# CPU.net
KiCad netlist of a schematic drawn in Altium Designer
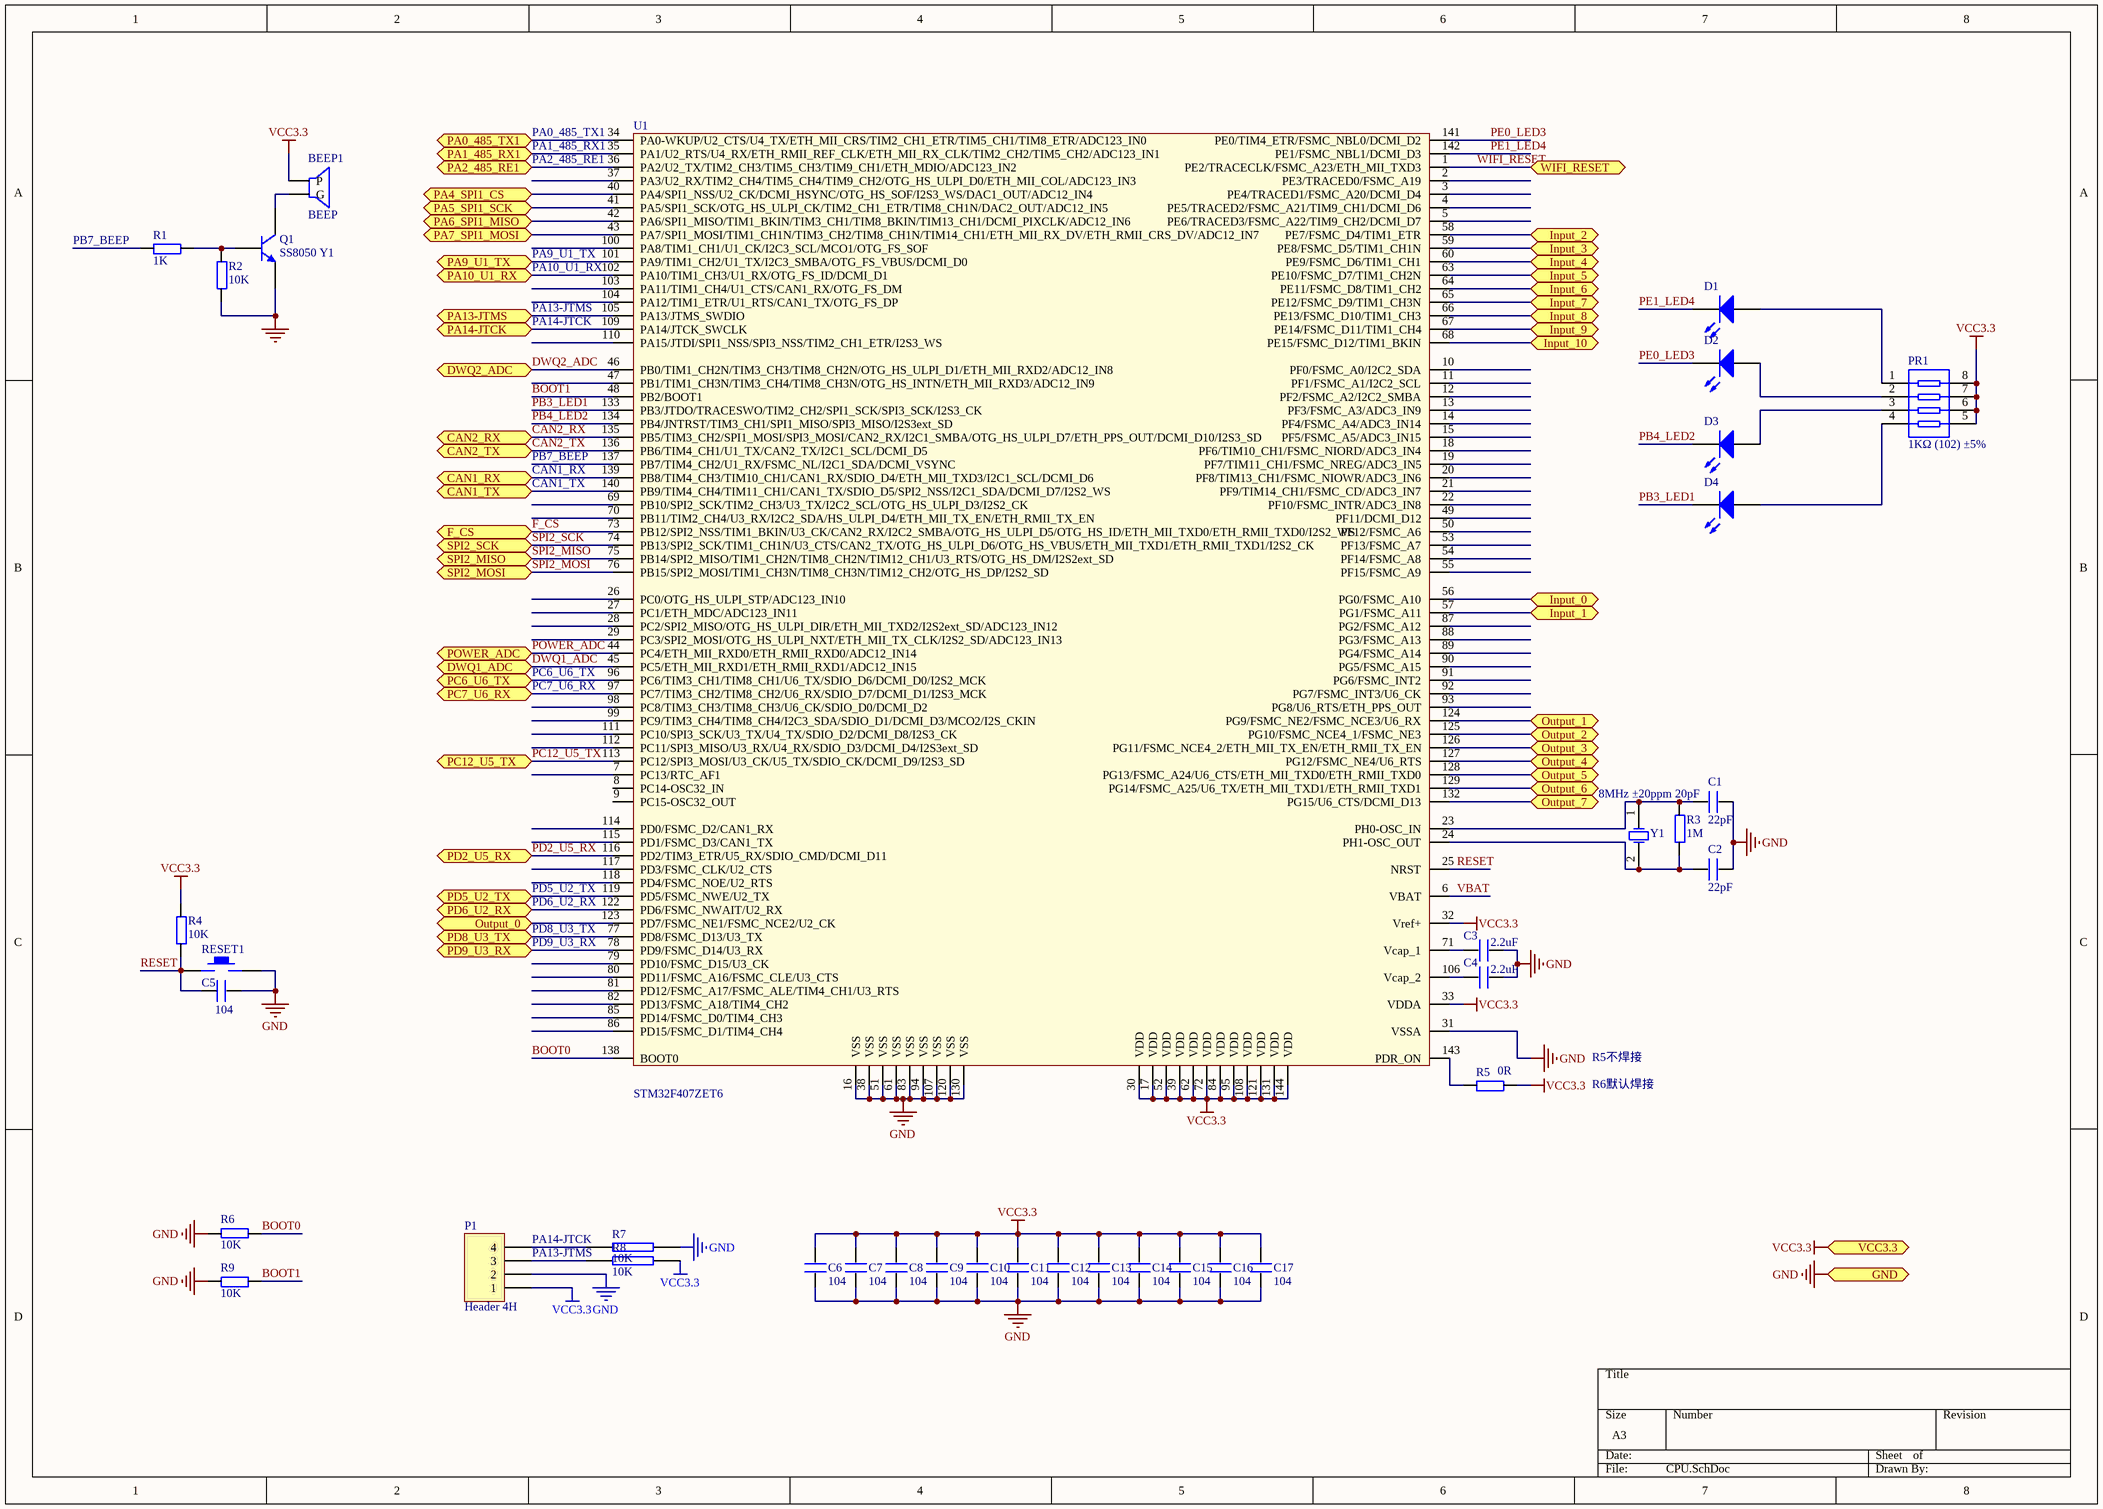
[diagram p0: CPU.SchDoc]

(export (version "E")
  (design (tool "Eeschema 10.0.6"))
  (components
    (comp (ref "BEEP1") (value "BEEP") (footprint "BELL-5") (libsource (lib "WarShip V3_SCH") (part "BEEP")))
    (comp (ref "C1")
      (value "22pF")
      (footprint "0603_C")
      (libsource (lib "Explorer STM32F407封装库") (part "C_3"))
    )
    (comp (ref "C2")
      (value "22pF")
      (footprint "0603_C")
      (libsource (lib "Explorer STM32F407封装库") (part "C_3"))
    )
    (comp (ref "C3")
      (value "2.2uF")
      (footprint "0603_C")
      (libsource (lib "Explorer STM32F407封装库") (part "C"))
    )
    (comp (ref "C4")
      (value "2.2uF")
      (footprint "0603_C")
      (libsource (lib "Explorer STM32F407封装库") (part "C"))
    )
    (comp (ref "C5") (value "104") (footprint "0603_C") (libsource (lib "Explorer STM32F407封装库") (part "C")))
    (comp (ref "C6") (value "104") (footprint "0603_C") (libsource (lib "WarShip V3_SCH") (part "C")))
    (comp (ref "C7") (value "104") (footprint "0603_C") (libsource (lib "WarShip V3_SCH") (part "C")))
    (comp (ref "C8") (value "104") (footprint "0603_C") (libsource (lib "WarShip V3_SCH") (part "C")))
    (comp (ref "C9") (value "104") (footprint "0603_C") (libsource (lib "WarShip V3_SCH") (part "C")))
    (comp (ref "C10") (value "104") (footprint "0603_C") (libsource (lib "WarShip V3_SCH") (part "C")))
    (comp (ref "C11") (value "104") (footprint "0603_C") (libsource (lib "WarShip V3_SCH") (part "C")))
    (comp (ref "C12") (value "104") (footprint "0603_C") (libsource (lib "WarShip V3_SCH") (part "C")))
    (comp (ref "C13") (value "104") (footprint "0603_C") (libsource (lib "WarShip V3_SCH") (part "C")))
    (comp (ref "C14") (value "104") (footprint "0603_C") (libsource (lib "WarShip V3_SCH") (part "C")))
    (comp (ref "C15") (value "104") (footprint "0603_C") (libsource (lib "WarShip V3_SCH") (part "C")))
    (comp (ref "C16") (value "104") (footprint "0603_C") (libsource (lib "WarShip V3_SCH") (part "C")))
    (comp (ref "C17") (value "104") (footprint "0603_C") (libsource (lib "WarShip V3_SCH") (part "C")))
    (comp (ref "D1")
      (value "红灯 0805")
      (footprint "LC-0805_LED_S1")
      (description "Typical INFRARED GaAs LED")
      (fields (field (name "PUBLISHER") "Altium Limited"))
      (libsource (lib "继电器板_1") (part "LED0"))
    )
    (comp (ref "D2")
      (value "红灯 0805")
      (footprint "LC-0805_LED_S1")
      (description "Typical INFRARED GaAs LED")
      (fields (field (name "PUBLISHER") "Altium Limited"))
      (libsource (lib "继电器板_1") (part "LED0"))
    )
    (comp (ref "D3")
      (value "红灯 0805")
      (footprint "LC-0805_LED_S1")
      (description "Typical INFRARED GaAs LED")
      (fields (field (name "PUBLISHER") "Altium Limited"))
      (libsource (lib "继电器板_1") (part "LED0"))
    )
    (comp (ref "D4")
      (value "红灯 0805")
      (footprint "LC-0805_LED_S1")
      (description "Typical INFRARED GaAs LED")
      (fields (field (name "PUBLISHER") "Altium Limited"))
      (libsource (lib "继电器板_1") (part "LED0"))
    )
    (comp (ref "P1")
      (value "Header 4H")
      (footprint "IDE4")
      (description "Header, 4-Pin, Right Angle")
      (fields (field (name "PUBLISHER") "Altium Limited"))
      (libsource (lib "Miscellaneous Connectors") (part "Header 4H"))
    )
    (comp (ref "PR1")
      (value "1KΩ (102) ±5%")
      (footprint "0603_Rx4")
      (description "贴片排阻")
      (libsource (lib "Miscellaneous Devices LC") (part "0603*4  1KΩ (102) 5%"))
    )
    (comp (ref "Q1")
      (value "SS8050 Y1")
      (footprint "SOT-23(SOT-23-3)")
      (description "三极管")
      (libsource (lib "Miscellaneous Devices LC") (part "SOT-23 SS8050 Y1"))
    )
    (comp (ref "R1") (value "1K") (footprint "0603_R") (libsource (lib "WarShip V3_SCH") (part "R")))
    (comp (ref "R2") (value "10K") (footprint "0603_R") (libsource (lib "WarShip V3_SCH") (part "R")))
    (comp (ref "R3") (value "1M") (footprint "0603_R") (libsource (lib "Explorer STM32F407封装库") (part "R")))
    (comp (ref "R4")
      (value "10K")
      (footprint "0603_R")
      (libsource (lib "Explorer STM32F407封装库") (part "R_2"))
    )
    (comp (ref "R5") (value "0R") (footprint "0603_R") (libsource (lib "Explorer STM32F407封装库") (part "R_2")))
    (comp (ref "R6")
      (value "10K")
      (footprint "0603_R")
      (libsource (lib "Explorer STM32F407封装库") (part "R_1"))
    )
    (comp (ref "R7") (value "10K") (footprint "0603_R") (libsource (lib "*") (part "RES2")))
    (comp (ref "R8") (value "10K") (footprint "0603_R") (libsource (lib "*") (part "RES2")))
    (comp (ref "R9")
      (value "10K")
      (footprint "0603_R")
      (libsource (lib "Explorer STM32F407封装库") (part "R_1"))
    )
    (comp (ref "RESET1")
      (value "KEY_M")
      (footprint "SW_PB2_A1")
      (libsource (lib "Explorer STM32F407封装库") (part "KEY_M"))
    )
    (comp (ref "U1")
      (value "STM32F407ZET6")
      (footprint "LQFP-144_20x20x05P")
      (libsource (lib "Explorer STM32F407封装库") (part "STM32F407ZET6"))
    )
    (comp (ref "Y1")
      (value "8MHz ±20ppm 20pF")
      (footprint "SMD-5032_2P")
      (description "贴片晶振")
      (libsource (lib "Miscellaneous Devices LC") (part "SMD-5032_2P 8MHz 20ppm 20pF"))
    )
  )
  (nets
    (net (code "1") (name "/BOOT0") (class "Default")
      (node (ref "R6") (pin "1") (pintype "passive"))
      (node (ref "U1") (pin "138") (pinfunction "BOOT0_138") (pintype "passive"))
    )
    (net (code "2") (name "/BOOT1") (class "Default")
      (node (ref "R9") (pin "2") (pintype "passive"))
      (node (ref "U1") (pin "48") (pinfunction "PB2/BOOT1_48") (pintype "passive"))
    )
    (net (code "3") (name "/CAN1_RX") (class "Default")
      (node (ref "U1") (pin "139") (pinfunction "PB8/TIM4_CH3/TIM10_CH1/CAN1_RX/SDIO_D4/ETH_MII_TXD3/I2C1_SCL/DCMI_D6_139") (pintype "passive"))
    )
    (net (code "4") (name "/CAN1_TX") (class "Default")
      (node (ref "U1") (pin "140") (pinfunction "PB9/TIM4_CH4/TIM11_CH1/CAN1_TX/SDIO_D5/SPI2_NSS/I2C1_SDA/DCMI_D7/I2S2_WS_140") (pintype "passive"))
    )
    (net (code "5") (name "/CAN2_RX") (class "Default")
      (node (ref "U1") (pin "135") (pinfunction "PB5/TIM3_CH2/SPI1_MOSI/SPI3_MOSI/CAN2_RX/I2C1_SMBA/OTG_HS_ULPI_D7/ETH_PPS_OUT/DCMI_D10/I2S3_SD_135") (pintype "passive"))
    )
    (net (code "6") (name "/CAN2_TX") (class "Default")
      (node (ref "U1") (pin "136") (pinfunction "PB6/TIM4_CH1/U1_TX/CAN2_TX/I2C1_SCL/DCMI_D5_136") (pintype "passive"))
    )
    (net (code "7") (name "/DWQ1_ADC") (class "Default")
      (node (ref "U1") (pin "45") (pinfunction "PC5/ETH_MII_RXD1/ETH_RMII_RXD1/ADC12_IN15_45") (pintype "passive"))
    )
    (net (code "8") (name "/DWQ2_ADC") (class "Default")
      (node (ref "U1") (pin "46") (pinfunction "PB0/TIM1_CH2N/TIM3_CH3/TIM8_CH2N/OTG_HS_ULPI_D1/ETH_MII_RXD2/ADC12_IN8_46") (pintype "passive"))
    )
    (net (code "9") (name "/F_CS") (class "Default")
      (node (ref "U1") (pin "73") (pinfunction "PB12/SPI2_NSS/TIM1_BKIN/U3_CK/CAN2_RX/I2C2_SMBA/OTG_HS_ULPI_D5/OTG_HS_ID/ETH_MII_TXD0/ETH_RMII_TXD0/I2S2_WS_73") (pintype "passive"))
    )
    (net (code "10") (name "/Input_0") (class "Default")
      (node (ref "U1") (pin "56") (pinfunction "PG0/FSMC_A10_56") (pintype "passive"))
    )
    (net (code "11") (name "/Input_1") (class "Default")
      (node (ref "U1") (pin "57") (pinfunction "PG1/FSMC_A11_57") (pintype "passive"))
    )
    (net (code "12") (name "/Input_2") (class "Default")
      (node (ref "U1") (pin "58") (pinfunction "PE7/FSMC_D4/TIM1_ETR_58") (pintype "passive"))
    )
    (net (code "13") (name "/Input_3") (class "Default")
      (node (ref "U1") (pin "59") (pinfunction "PE8/FSMC_D5/TIM1_CH1N_59") (pintype "passive"))
    )
    (net (code "14") (name "/Input_4") (class "Default")
      (node (ref "U1") (pin "60") (pinfunction "PE9/FSMC_D6/TIM1_CH1_60") (pintype "passive"))
    )
    (net (code "15") (name "/Input_5") (class "Default")
      (node (ref "U1") (pin "63") (pinfunction "PE10/FSMC_D7/TIM1_CH2N_63") (pintype "passive"))
    )
    (net (code "16") (name "/Input_6") (class "Default")
      (node (ref "U1") (pin "64") (pinfunction "PE11/FSMC_D8/TIM1_CH2_64") (pintype "passive"))
    )
    (net (code "17") (name "/Input_7") (class "Default")
      (node (ref "U1") (pin "65") (pinfunction "PE12/FSMC_D9/TIM1_CH3N_65") (pintype "passive"))
    )
    (net (code "18") (name "/Input_8") (class "Default")
      (node (ref "U1") (pin "66") (pinfunction "PE13/FSMC_D10/TIM1_CH3_66") (pintype "passive"))
    )
    (net (code "19") (name "/Input_9") (class "Default")
      (node (ref "U1") (pin "67") (pinfunction "PE14/FSMC_D11/TIM1_CH4_67") (pintype "passive"))
    )
    (net (code "20") (name "/Input_10") (class "Default")
      (node (ref "U1") (pin "68") (pinfunction "PE15/FSMC_D12/TIM1_BKIN_68") (pintype "passive"))
    )
    (net (code "21") (name "/Output_0") (class "Default")
      (node (ref "U1") (pin "123") (pinfunction "PD7/FSMC_NE1/FSMC_NCE2/U2_CK_123") (pintype "passive"))
    )
    (net (code "22") (name "/Output_1") (class "Default")
      (node (ref "U1") (pin "124") (pinfunction "PG9/FSMC_NE2/FSMC_NCE3/U6_RX_124") (pintype "passive"))
    )
    (net (code "23") (name "/Output_2") (class "Default")
      (node (ref "U1") (pin "125") (pinfunction "PG10/FSMC_NCE4_1/FSMC_NE3_125") (pintype "passive"))
    )
    (net (code "24") (name "/Output_3") (class "Default")
      (node (ref "U1") (pin "126") (pinfunction "PG11/FSMC_NCE4_2/ETH_MII_TX_EN/ETH_RMII_TX_EN_126") (pintype "passive"))
    )
    (net (code "25") (name "/Output_4") (class "Default")
      (node (ref "U1") (pin "127") (pinfunction "PG12/FSMC_NE4/U6_RTS_127") (pintype "passive"))
    )
    (net (code "26") (name "/Output_5") (class "Default")
      (node (ref "U1") (pin "128") (pinfunction "PG13/FSMC_A24/U6_CTS/ETH_MII_TXD0/ETH_RMII_TXD0_128") (pintype "passive"))
    )
    (net (code "27") (name "/Output_6") (class "Default")
      (node (ref "U1") (pin "129") (pinfunction "PG14/FSMC_A25/U6_TX/ETH_MII_TXD1/ETH_RMII_TXD1_129") (pintype "passive"))
    )
    (net (code "28") (name "/Output_7") (class "Default")
      (node (ref "U1") (pin "132") (pinfunction "PG15/U6_CTS/DCMI_D13_132") (pintype "passive"))
    )
    (net (code "29") (name "/PA0_485_TX1") (class "Default")
      (node (ref "U1") (pin "34") (pinfunction "PA0-WKUP/U2_CTS/U4_TX/ETH_MII_CRS/TIM2_CH1_ETR/TIM5_CH1/TIM8_ETR/ADC123_IN0_34") (pintype "passive"))
    )
    (net (code "30") (name "/PA1_485_RX1") (class "Default")
      (node (ref "U1") (pin "35") (pinfunction "PA1/U2_RTS/U4_RX/ETH_RMII_REF_CLK/ETH_MII_RX_CLK/TIM2_CH2/TIM5_CH2/ADC123_IN1_35") (pintype "passive"))
    )
    (net (code "31") (name "/PA2_485_RE1") (class "Default")
      (node (ref "U1") (pin "36") (pinfunction "PA2/U2_TX/TIM2_CH3/TIM5_CH3/TIM9_CH1/ETH_MDIO/ADC123_IN2_36") (pintype "passive"))
    )
    (net (code "32") (name "/PA4_SPI1_CS") (class "Default")
      (node (ref "U1") (pin "40") (pinfunction "PA4/SPI1_NSS/U2_CK/DCMI_HSYNC/OTG_HS_SOF/I2S3_WS/DAC1_OUT/ADC12_IN4_40") (pintype "passive"))
    )
    (net (code "33") (name "/PA5_SPI1_SCK") (class "Default")
      (node (ref "U1") (pin "41") (pinfunction "PA5/SPI1_SCK/OTG_HS_ULPI_CK/TIM2_CH1_ETR/TIM8_CH1N/DAC2_OUT/ADC12_IN5_41") (pintype "passive"))
    )
    (net (code "34") (name "/PA6_SPI1_MISO") (class "Default")
      (node (ref "U1") (pin "42") (pinfunction "PA6/SPI1_MISO/TIM1_BKIN/TIM3_CH1/TIM8_BKIN/TIM13_CH1/DCMI_PIXCLK/ADC12_IN6_42") (pintype "passive"))
    )
    (net (code "35") (name "/PA7_SPI1_MOSI") (class "Default")
      (node (ref "U1") (pin "43") (pinfunction "PA7/SPI1_MOSI/TIM1_CH1N/TIM3_CH2/TIM8_CH1N/TIM14_CH1/ETH_MII_RX_DV/ETH_RMII_CRS_DV/ADC12_IN7_43") (pintype "passive"))
    )
    (net (code "36") (name "/PA9_U1_TX") (class "Default")
      (node (ref "U1") (pin "101") (pinfunction "PA9/TIM1_CH2/U1_TX/I2C3_SMBA/OTG_FS_VBUS/DCMI_D0_101") (pintype "passive"))
    )
    (net (code "37") (name "/PA10_U1_RX") (class "Default")
      (node (ref "U1") (pin "102") (pinfunction "PA10/TIM1_CH3/U1_RX/OTG_FS_ID/DCMI_D1_102") (pintype "passive"))
    )
    (net (code "38") (name "/PA13-JTMS") (class "Default")
      (node (ref "P1") (pin "3") (pinfunction "3_3") (pintype "passive"))
      (node (ref "R8") (pin "2") (pinfunction "2_2") (pintype "passive"))
      (node (ref "U1") (pin "105") (pinfunction "PA13/JTMS_SWDIO_105") (pintype "passive"))
    )
    (net (code "39") (name "/PA14-JTCK") (class "Default")
      (node (ref "P1") (pin "4") (pinfunction "4_4") (pintype "passive"))
      (node (ref "R7") (pin "2") (pinfunction "2_2") (pintype "passive"))
      (node (ref "U1") (pin "109") (pinfunction "PA14/JTCK_SWCLK_109") (pintype "passive"))
    )
    (net (code "40") (name "/PB3_LED1") (class "Default")
      (node (ref "D4") (pin "K") (pinfunction "K_K") (pintype "passive"))
      (node (ref "U1") (pin "133") (pinfunction "PB3/JTDO/TRACESWO/TIM2_CH2/SPI1_SCK/SPI3_SCK/I2S3_CK_133") (pintype "passive"))
    )
    (net (code "41") (name "/PB4_LED2") (class "Default")
      (node (ref "D3") (pin "K") (pinfunction "K_K") (pintype "passive"))
      (node (ref "U1") (pin "134") (pinfunction "PB4/JNTRST/TIM3_CH1/SPI1_MISO/SPI3_MISO/I2S3ext_SD_134") (pintype "passive"))
    )
    (net (code "42") (name "/PB7_BEEP") (class "Default")
      (node (ref "R1") (pin "1") (pintype "passive"))
      (node (ref "U1") (pin "137") (pinfunction "PB7/TIM4_CH2/U1_RX/FSMC_NL/I2C1_SDA/DCMI_VSYNC_137") (pintype "passive"))
    )
    (net (code "43") (name "/PC6_U6_TX") (class "Default")
      (node (ref "U1") (pin "96") (pinfunction "PC6/TIM3_CH1/TIM8_CH1/U6_TX/SDIO_D6/DCMI_D0/I2S2_MCK_96") (pintype "passive"))
    )
    (net (code "44") (name "/PC7_U6_RX") (class "Default")
      (node (ref "U1") (pin "97") (pinfunction "PC7/TIM3_CH2/TIM8_CH2/U6_RX/SDIO_D7/DCMI_D1/I2S3_MCK_97") (pintype "passive"))
    )
    (net (code "45") (name "/PC12_U5_TX") (class "Default")
      (node (ref "U1") (pin "113") (pinfunction "PC12/SPI3_MOSI/U3_CK/U5_TX/SDIO_CK/DCMI_D9/I2S3_SD_113") (pintype "passive"))
    )
    (net (code "46") (name "/PD2_U5_RX") (class "Default")
      (node (ref "U1") (pin "116") (pinfunction "PD2/TIM3_ETR/U5_RX/SDIO_CMD/DCMI_D11_116") (pintype "passive"))
    )
    (net (code "47") (name "/PD5_U2_TX") (class "Default")
      (node (ref "U1") (pin "119") (pinfunction "PD5/FSMC_NWE/U2_TX_119") (pintype "passive"))
    )
    (net (code "48") (name "/PD6_U2_RX") (class "Default")
      (node (ref "U1") (pin "122") (pinfunction "PD6/FSMC_NWAIT/U2_RX_122") (pintype "passive"))
    )
    (net (code "49") (name "/PD8_U3_TX") (class "Default")
      (node (ref "U1") (pin "77") (pinfunction "PD8/FSMC_D13/U3_TX_77") (pintype "passive"))
    )
    (net (code "50") (name "/PD9_U3_RX") (class "Default")
      (node (ref "U1") (pin "78") (pinfunction "PD9/FSMC_D14/U3_RX_78") (pintype "passive"))
    )
    (net (code "51") (name "/PE0_LED3") (class "Default")
      (node (ref "D2") (pin "K") (pinfunction "K_K") (pintype "passive"))
      (node (ref "U1") (pin "141") (pinfunction "PE0/TIM4_ETR/FSMC_NBL0/DCMI_D2_141") (pintype "passive"))
    )
    (net (code "52") (name "/PE1_LED4") (class "Default")
      (node (ref "D1") (pin "K") (pinfunction "K_K") (pintype "passive"))
      (node (ref "U1") (pin "142") (pinfunction "PE1/FSMC_NBL1/DCMI_D3_142") (pintype "passive"))
    )
    (net (code "53") (name "/POWER_ADC") (class "Default")
      (node (ref "U1") (pin "44") (pinfunction "PC4/ETH_MII_RXD0/ETH_RMII_RXD0/ADC12_IN14_44") (pintype "passive"))
    )
    (net (code "54") (name "/RESET") (class "Default")
      (node (ref "C5") (pin "1") (pintype "passive"))
      (node (ref "R4") (pin "1") (pintype "passive"))
      (node (ref "RESET1") (pin "1") (pinfunction "1_1") (pintype "passive"))
      (node (ref "U1") (pin "25") (pinfunction "NRST_25") (pintype "passive"))
    )
    (net (code "55") (name "/SPI2_MISO") (class "Default")
      (node (ref "U1") (pin "75") (pinfunction "PB14/SPI2_MISO/TIM1_CH2N/TIM8_CH2N/TIM12_CH1/U3_RTS/OTG_HS_DM/I2S2ext_SD_75") (pintype "passive"))
    )
    (net (code "56") (name "/SPI2_MOSI") (class "Default")
      (node (ref "U1") (pin "76") (pinfunction "PB15/SPI2_MOSI/TIM1_CH3N/TIM8_CH3N/TIM12_CH2/OTG_HS_DP/I2S2_SD_76") (pintype "passive"))
    )
    (net (code "57") (name "/SPI2_SCK") (class "Default")
      (node (ref "U1") (pin "74") (pinfunction "PB13/SPI2_SCK/TIM1_CH1N/U3_CTS/CAN2_TX/OTG_HS_ULPI_D6/OTG_HS_VBUS/ETH_MII_TXD1/ETH_RMII_TXD1/I2S2_CK_74") (pintype "passive"))
    )
    (net (code "58") (name "/VBAT") (class "Default")
      (node (ref "U1") (pin "6") (pinfunction "VBAT_6") (pintype "passive"))
    )
    (net (code "59") (name "/WIFI_RESET") (class "Default")
      (node (ref "U1") (pin "1") (pinfunction "PE2/TRACECLK/FSMC_A23/ETH_MII_TXD3_1") (pintype "passive"))
    )
    (net (code "60") (name "GND") (class "Default")
      (node (ref "C1") (pin "1") (pintype "passive"))
      (node (ref "C10") (pin "1") (pintype "passive"))
      (node (ref "C11") (pin "1") (pintype "passive"))
      (node (ref "C12") (pin "1") (pintype "passive"))
      (node (ref "C13") (pin "1") (pintype "passive"))
      (node (ref "C14") (pin "1") (pintype "passive"))
      (node (ref "C15") (pin "1") (pintype "passive"))
      (node (ref "C16") (pin "1") (pintype "passive"))
      (node (ref "C17") (pin "1") (pintype "passive"))
      (node (ref "C2") (pin "1") (pintype "passive"))
      (node (ref "C3") (pin "2") (pintype "passive"))
      (node (ref "C4") (pin "2") (pintype "passive"))
      (node (ref "C5") (pin "2") (pintype "passive"))
      (node (ref "C6") (pin "1") (pintype "passive"))
      (node (ref "C7") (pin "1") (pintype "passive"))
      (node (ref "C8") (pin "1") (pintype "passive"))
      (node (ref "C9") (pin "1") (pintype "passive"))
      (node (ref "P1") (pin "2") (pinfunction "2_2") (pintype "passive"))
      (node (ref "Q1") (pin "2") (pinfunction "E_2") (pintype "passive"))
      (node (ref "R2") (pin "1") (pintype "passive"))
      (node (ref "R6") (pin "2") (pintype "passive"))
      (node (ref "R7") (pin "1") (pinfunction "1_1") (pintype "passive"))
      (node (ref "R9") (pin "1") (pintype "passive"))
      (node (ref "RESET1") (pin "2") (pinfunction "2_2") (pintype "passive"))
      (node (ref "U1") (pin "107") (pinfunction "VSS_107") (pintype "passive"))
      (node (ref "U1") (pin "120") (pinfunction "VSS_120") (pintype "passive"))
      (node (ref "U1") (pin "130") (pinfunction "VSS_130") (pintype "passive"))
      (node (ref "U1") (pin "16") (pinfunction "VSS_16") (pintype "passive"))
      (node (ref "U1") (pin "31") (pinfunction "VSSA_31") (pintype "passive"))
      (node (ref "U1") (pin "38") (pinfunction "VSS_38") (pintype "passive"))
      (node (ref "U1") (pin "51") (pinfunction "VSS_51") (pintype "passive"))
      (node (ref "U1") (pin "61") (pinfunction "VSS_61") (pintype "passive"))
      (node (ref "U1") (pin "83") (pinfunction "VSS_83") (pintype "passive"))
      (node (ref "U1") (pin "94") (pinfunction "VSS_94") (pintype "passive"))
    )
    (net (code "61") (name "Net-(BEEP1-G)") (class "Default")
      (node (ref "BEEP1") (pin "2") (pinfunction "G_2") (pintype "passive"))
      (node (ref "Q1") (pin "3") (pinfunction "C_3") (pintype "passive"))
    )
    (net (code "62") (name "Net-(D1-PadA)") (class "Default")
      (node (ref "D1") (pin "A") (pinfunction "A_A") (pintype "passive"))
      (node (ref "PR1") (pin "1") (pinfunction "1_1") (pintype "passive"))
    )
    (net (code "63") (name "Net-(D2-PadA)") (class "Default")
      (node (ref "D2") (pin "A") (pinfunction "A_A") (pintype "passive"))
      (node (ref "PR1") (pin "2") (pinfunction "2_2") (pintype "passive"))
    )
    (net (code "64") (name "Net-(D3-PadA)") (class "Default")
      (node (ref "D3") (pin "A") (pinfunction "A_A") (pintype "passive"))
      (node (ref "PR1") (pin "3") (pinfunction "3_3") (pintype "passive"))
    )
    (net (code "65") (name "Net-(D4-PadA)") (class "Default")
      (node (ref "D4") (pin "A") (pinfunction "A_A") (pintype "passive"))
      (node (ref "PR1") (pin "4") (pinfunction "4_4") (pintype "passive"))
    )
    (net (code "66") (name "Net-(Q1-B)") (class "Default")
      (node (ref "Q1") (pin "1") (pinfunction "B_1") (pintype "passive"))
      (node (ref "R1") (pin "2") (pintype "passive"))
      (node (ref "R2") (pin "2") (pintype "passive"))
    )
    (net (code "67") (name "Net-(U1-PDR_ON)") (class "Default")
      (node (ref "R5") (pin "1") (pintype "passive"))
      (node (ref "U1") (pin "143") (pinfunction "PDR_ON_143") (pintype "passive"))
    )
    (net (code "68") (name "Net-(U1-PH0-OSC_IN)") (class "Default")
      (node (ref "C1") (pin "2") (pintype "passive"))
      (node (ref "R3") (pin "2") (pintype "passive"))
      (node (ref "U1") (pin "23") (pinfunction "PH0-OSC_IN_23") (pintype "passive"))
      (node (ref "Y1") (pin "1") (pinfunction "OSC1_1") (pintype "passive"))
    )
    (net (code "69") (name "Net-(U1-PH1-OSC_OUT)") (class "Default")
      (node (ref "C2") (pin "2") (pintype "passive"))
      (node (ref "R3") (pin "1") (pintype "passive"))
      (node (ref "U1") (pin "24") (pinfunction "PH1-OSC_OUT_24") (pintype "passive"))
      (node (ref "Y1") (pin "2") (pinfunction "OSC2_2") (pintype "passive"))
    )
    (net (code "70") (name "Net-(U1-Vcap_1)") (class "Default")
      (node (ref "C3") (pin "1") (pintype "passive"))
      (node (ref "U1") (pin "71") (pinfunction "Vcap_1_71") (pintype "passive"))
    )
    (net (code "71") (name "Net-(U1-Vcap_2)") (class "Default")
      (node (ref "C4") (pin "1") (pintype "passive"))
      (node (ref "U1") (pin "106") (pinfunction "Vcap_2_106") (pintype "passive"))
    )
    (net (code "72") (name "VCC3.3") (class "Default")
      (node (ref "BEEP1") (pin "1") (pinfunction "P_1") (pintype "passive"))
      (node (ref "C10") (pin "2") (pintype "passive"))
      (node (ref "C11") (pin "2") (pintype "passive"))
      (node (ref "C12") (pin "2") (pintype "passive"))
      (node (ref "C13") (pin "2") (pintype "passive"))
      (node (ref "C14") (pin "2") (pintype "passive"))
      (node (ref "C15") (pin "2") (pintype "passive"))
      (node (ref "C16") (pin "2") (pintype "passive"))
      (node (ref "C17") (pin "2") (pintype "passive"))
      (node (ref "C6") (pin "2") (pintype "passive"))
      (node (ref "C7") (pin "2") (pintype "passive"))
      (node (ref "C8") (pin "2") (pintype "passive"))
      (node (ref "C9") (pin "2") (pintype "passive"))
      (node (ref "P1") (pin "1") (pinfunction "1_1") (pintype "passive"))
      (node (ref "PR1") (pin "5") (pinfunction "5_5") (pintype "passive"))
      (node (ref "PR1") (pin "6") (pinfunction "6_6") (pintype "passive"))
      (node (ref "PR1") (pin "7") (pinfunction "7_7") (pintype "passive"))
      (node (ref "PR1") (pin "8") (pinfunction "8_8") (pintype "passive"))
      (node (ref "R4") (pin "2") (pintype "passive"))
      (node (ref "R5") (pin "2") (pintype "passive"))
      (node (ref "R8") (pin "1") (pinfunction "1_1") (pintype "passive"))
      (node (ref "U1") (pin "108") (pinfunction "VDD_108") (pintype "passive"))
      (node (ref "U1") (pin "121") (pinfunction "VDD_121") (pintype "passive"))
      (node (ref "U1") (pin "131") (pinfunction "VDD_131") (pintype "passive"))
      (node (ref "U1") (pin "144") (pinfunction "VDD_144") (pintype "passive"))
      (node (ref "U1") (pin "17") (pinfunction "VDD_17") (pintype "passive"))
      (node (ref "U1") (pin "30") (pinfunction "VDD_30") (pintype "passive"))
      (node (ref "U1") (pin "32") (pinfunction "Vref+_32") (pintype "passive"))
      (node (ref "U1") (pin "33") (pinfunction "VDDA_33") (pintype "passive"))
      (node (ref "U1") (pin "39") (pinfunction "VDD_39") (pintype "passive"))
      (node (ref "U1") (pin "52") (pinfunction "VDD_52") (pintype "passive"))
      (node (ref "U1") (pin "62") (pinfunction "VDD_62") (pintype "passive"))
      (node (ref "U1") (pin "72") (pinfunction "VDD_72") (pintype "passive"))
      (node (ref "U1") (pin "84") (pinfunction "VDD_84") (pintype "passive"))
      (node (ref "U1") (pin "95") (pinfunction "VDD_95") (pintype "passive"))
    )
    (net (code "73") (name "unconnected-(U1-PA3{slash}U2_RX{slash}TIM2_CH4{slash}TIM5_CH4{slash}TIM9_CH2{slash}OTG_HS_ULPI_D0{slash}ETH_MII_COL{slash}ADC123_IN3-Pad37)") (class "Default")
      (node (ref "U1") (pin "37") (pinfunction "PA3/U2_RX/TIM2_CH4/TIM5_CH4/TIM9_CH2/OTG_HS_ULPI_D0/ETH_MII_COL/ADC123_IN3_37") (pintype "passive"))
    )
    (net (code "74") (name "unconnected-(U1-PA8{slash}TIM1_CH1{slash}U1_CK{slash}I2C3_SCL{slash}MCO1{slash}OTG_FS_SOF-Pad100)") (class "Default")
      (node (ref "U1") (pin "100") (pinfunction "PA8/TIM1_CH1/U1_CK/I2C3_SCL/MCO1/OTG_FS_SOF_100") (pintype "passive"))
    )
    (net (code "75") (name "unconnected-(U1-PA11{slash}TIM1_CH4{slash}U1_CTS{slash}CAN1_RX{slash}OTG_FS_DM-Pad103)") (class "Default")
      (node (ref "U1") (pin "103") (pinfunction "PA11/TIM1_CH4/U1_CTS/CAN1_RX/OTG_FS_DM_103") (pintype "passive"))
    )
    (net (code "76") (name "unconnected-(U1-PA12{slash}TIM1_ETR{slash}U1_RTS{slash}CAN1_TX{slash}OTG_FS_DP-Pad104)") (class "Default")
      (node (ref "U1") (pin "104") (pinfunction "PA12/TIM1_ETR/U1_RTS/CAN1_TX/OTG_FS_DP_104") (pintype "passive"))
    )
    (net (code "77") (name "unconnected-(U1-PA15{slash}JTDI{slash}SPI1_NSS{slash}SPI3_NSS{slash}TIM2_CH1_ETR{slash}I2S3_WS-Pad110)") (class "Default")
      (node (ref "U1") (pin "110") (pinfunction "PA15/JTDI/SPI1_NSS/SPI3_NSS/TIM2_CH1_ETR/I2S3_WS_110") (pintype "passive"))
    )
    (net (code "78") (name "unconnected-(U1-PB1{slash}TIM1_CH3N{slash}TIM3_CH4{slash}TIM8_CH3N{slash}OTG_HS_INTN{slash}ETH_MII_RXD3{slash}ADC12_IN9-Pad47)") (class "Default")
      (node (ref "U1") (pin "47") (pinfunction "PB1/TIM1_CH3N/TIM3_CH4/TIM8_CH3N/OTG_HS_INTN/ETH_MII_RXD3/ADC12_IN9_47") (pintype "passive"))
    )
    (net (code "79") (name "unconnected-(U1-PB10{slash}SPI2_SCK{slash}TIM2_CH3{slash}U3_TX{slash}I2C2_SCL{slash}OTG_HS_ULPI_D3{slash}I2S2_CK-Pad69)") (class "Default")
      (node (ref "U1") (pin "69") (pinfunction "PB10/SPI2_SCK/TIM2_CH3/U3_TX/I2C2_SCL/OTG_HS_ULPI_D3/I2S2_CK_69") (pintype "passive"))
    )
    (net (code "80") (name "unconnected-(U1-PB11{slash}TIM2_CH4{slash}U3_RX{slash}I2C2_SDA{slash}HS_ULPI_D4{slash}ETH_MII_TX_EN{slash}ETH_RMII_TX_EN-Pad70)") (class "Default")
      (node (ref "U1") (pin "70") (pinfunction "PB11/TIM2_CH4/U3_RX/I2C2_SDA/HS_ULPI_D4/ETH_MII_TX_EN/ETH_RMII_TX_EN_70") (pintype "passive"))
    )
    (net (code "81") (name "unconnected-(U1-PC0{slash}OTG_HS_ULPI_STP{slash}ADC123_IN10-Pad26)") (class "Default")
      (node (ref "U1") (pin "26") (pinfunction "PC0/OTG_HS_ULPI_STP/ADC123_IN10_26") (pintype "passive"))
    )
    (net (code "82") (name "unconnected-(U1-PC1{slash}ETH_MDC{slash}ADC123_IN11-Pad27)") (class "Default")
      (node (ref "U1") (pin "27") (pinfunction "PC1/ETH_MDC/ADC123_IN11_27") (pintype "passive"))
    )
    (net (code "83") (name "unconnected-(U1-PC2{slash}SPI2_MISO{slash}OTG_HS_ULPI_DIR{slash}ETH_MII_TXD2{slash}I2S2ext_SD{slash}ADC123_IN12-Pad28)") (class "Default")
      (node (ref "U1") (pin "28") (pinfunction "PC2/SPI2_MISO/OTG_HS_ULPI_DIR/ETH_MII_TXD2/I2S2ext_SD/ADC123_IN12_28") (pintype "passive"))
    )
    (net (code "84") (name "unconnected-(U1-PC3{slash}SPI2_MOSI{slash}OTG_HS_ULPI_NXT{slash}ETH_MII_TX_CLK{slash}I2S2_SD{slash}ADC123_IN13-Pad29)") (class "Default")
      (node (ref "U1") (pin "29") (pinfunction "PC3/SPI2_MOSI/OTG_HS_ULPI_NXT/ETH_MII_TX_CLK/I2S2_SD/ADC123_IN13_29") (pintype "passive"))
    )
    (net (code "85") (name "unconnected-(U1-PC8{slash}TIM3_CH3{slash}TIM8_CH3{slash}U6_CK{slash}SDIO_D0{slash}DCMI_D2-Pad98)") (class "Default")
      (node (ref "U1") (pin "98") (pinfunction "PC8/TIM3_CH3/TIM8_CH3/U6_CK/SDIO_D0/DCMI_D2_98") (pintype "passive"))
    )
    (net (code "86") (name "unconnected-(U1-PC9{slash}TIM3_CH4{slash}TIM8_CH4{slash}I2C3_SDA{slash}SDIO_D1{slash}DCMI_D3{slash}MCO2{slash}I2S_CKIN-Pad99)") (class "Default")
      (node (ref "U1") (pin "99") (pinfunction "PC9/TIM3_CH4/TIM8_CH4/I2C3_SDA/SDIO_D1/DCMI_D3/MCO2/I2S_CKIN_99") (pintype "passive"))
    )
    (net (code "87") (name "unconnected-(U1-PC10{slash}SPI3_SCK{slash}U3_TX{slash}U4_TX{slash}SDIO_D2{slash}DCMI_D8{slash}I2S3_CK-Pad111)") (class "Default")
      (node (ref "U1") (pin "111") (pinfunction "PC10/SPI3_SCK/U3_TX/U4_TX/SDIO_D2/DCMI_D8/I2S3_CK_111") (pintype "passive"))
    )
    (net (code "88") (name "unconnected-(U1-PC11{slash}SPI3_MISO{slash}U3_RX{slash}U4_RX{slash}SDIO_D3{slash}DCMI_D4{slash}I2S3ext_SD-Pad112)") (class "Default")
      (node (ref "U1") (pin "112") (pinfunction "PC11/SPI3_MISO/U3_RX/U4_RX/SDIO_D3/DCMI_D4/I2S3ext_SD_112") (pintype "passive"))
    )
    (net (code "89") (name "unconnected-(U1-PC13{slash}RTC_AF1-Pad7)") (class "Default")
      (node (ref "U1") (pin "7") (pinfunction "PC13/RTC_AF1_7") (pintype "passive"))
    )
    (net (code "90") (name "unconnected-(U1-PC14-OSC32_IN-Pad8)") (class "Default")
      (node (ref "U1") (pin "8") (pinfunction "PC14-OSC32_IN_8") (pintype "passive"))
    )
    (net (code "91") (name "unconnected-(U1-PC15-OSC32_OUT-Pad9)") (class "Default")
      (node (ref "U1") (pin "9") (pinfunction "PC15-OSC32_OUT_9") (pintype "passive"))
    )
    (net (code "92") (name "unconnected-(U1-PD0{slash}FSMC_D2{slash}CAN1_RX-Pad114)") (class "Default")
      (node (ref "U1") (pin "114") (pinfunction "PD0/FSMC_D2/CAN1_RX_114") (pintype "passive"))
    )
    (net (code "93") (name "unconnected-(U1-PD1{slash}FSMC_D3{slash}CAN1_TX-Pad115)") (class "Default")
      (node (ref "U1") (pin "115") (pinfunction "PD1/FSMC_D3/CAN1_TX_115") (pintype "passive"))
    )
    (net (code "94") (name "unconnected-(U1-PD3{slash}FSMC_CLK{slash}U2_CTS-Pad117)") (class "Default")
      (node (ref "U1") (pin "117") (pinfunction "PD3/FSMC_CLK/U2_CTS_117") (pintype "passive"))
    )
    (net (code "95") (name "unconnected-(U1-PD4{slash}FSMC_NOE{slash}U2_RTS-Pad118)") (class "Default")
      (node (ref "U1") (pin "118") (pinfunction "PD4/FSMC_NOE/U2_RTS_118") (pintype "passive"))
    )
    (net (code "96") (name "unconnected-(U1-PD10{slash}FSMC_D15{slash}U3_CK-Pad79)") (class "Default")
      (node (ref "U1") (pin "79") (pinfunction "PD10/FSMC_D15/U3_CK_79") (pintype "passive"))
    )
    (net (code "97") (name "unconnected-(U1-PD11{slash}FSMC_A16{slash}FSMC_CLE{slash}U3_CTS-Pad80)") (class "Default")
      (node (ref "U1") (pin "80") (pinfunction "PD11/FSMC_A16/FSMC_CLE/U3_CTS_80") (pintype "passive"))
    )
    (net (code "98") (name "unconnected-(U1-PD12{slash}FSMC_A17{slash}FSMC_ALE{slash}TIM4_CH1{slash}U3_RTS-Pad81)") (class "Default")
      (node (ref "U1") (pin "81") (pinfunction "PD12/FSMC_A17/FSMC_ALE/TIM4_CH1/U3_RTS_81") (pintype "passive"))
    )
    (net (code "99") (name "unconnected-(U1-PD13{slash}FSMC_A18{slash}TIM4_CH2-Pad82)") (class "Default")
      (node (ref "U1") (pin "82") (pinfunction "PD13/FSMC_A18/TIM4_CH2_82") (pintype "passive"))
    )
    (net (code "100") (name "unconnected-(U1-PD14{slash}FSMC_D0{slash}TIM4_CH3-Pad85)") (class "Default")
      (node (ref "U1") (pin "85") (pinfunction "PD14/FSMC_D0/TIM4_CH3_85") (pintype "passive"))
    )
    (net (code "101") (name "unconnected-(U1-PD15{slash}FSMC_D1{slash}TIM4_CH4-Pad86)") (class "Default")
      (node (ref "U1") (pin "86") (pinfunction "PD15/FSMC_D1/TIM4_CH4_86") (pintype "passive"))
    )
    (net (code "102") (name "unconnected-(U1-PE3{slash}TRACED0{slash}FSMC_A19-Pad2)") (class "Default")
      (node (ref "U1") (pin "2") (pinfunction "PE3/TRACED0/FSMC_A19_2") (pintype "passive"))
    )
    (net (code "103") (name "unconnected-(U1-PE4{slash}TRACED1{slash}FSMC_A20{slash}DCMI_D4-Pad3)") (class "Default")
      (node (ref "U1") (pin "3") (pinfunction "PE4/TRACED1/FSMC_A20/DCMI_D4_3") (pintype "passive"))
    )
    (net (code "104") (name "unconnected-(U1-PE5{slash}TRACED2{slash}FSMC_A21{slash}TIM9_CH1{slash}DCMI_D6-Pad4)") (class "Default")
      (node (ref "U1") (pin "4") (pinfunction "PE5/TRACED2/FSMC_A21/TIM9_CH1/DCMI_D6_4") (pintype "passive"))
    )
    (net (code "105") (name "unconnected-(U1-PE6{slash}TRACED3{slash}FSMC_A22{slash}TIM9_CH2{slash}DCMI_D7-Pad5)") (class "Default")
      (node (ref "U1") (pin "5") (pinfunction "PE6/TRACED3/FSMC_A22/TIM9_CH2/DCMI_D7_5") (pintype "passive"))
    )
    (net (code "106") (name "unconnected-(U1-PF0{slash}FSMC_A0{slash}I2C2_SDA-Pad10)") (class "Default")
      (node (ref "U1") (pin "10") (pinfunction "PF0/FSMC_A0/I2C2_SDA_10") (pintype "passive"))
    )
    (net (code "107") (name "unconnected-(U1-PF1{slash}FSMC_A1{slash}I2C2_SCL-Pad11)") (class "Default")
      (node (ref "U1") (pin "11") (pinfunction "PF1/FSMC_A1/I2C2_SCL_11") (pintype "passive"))
    )
    (net (code "108") (name "unconnected-(U1-PF2{slash}FSMC_A2{slash}I2C2_SMBA-Pad12)") (class "Default")
      (node (ref "U1") (pin "12") (pinfunction "PF2/FSMC_A2/I2C2_SMBA_12") (pintype "passive"))
    )
    (net (code "109") (name "unconnected-(U1-PF3{slash}FSMC_A3{slash}ADC3_IN9-Pad13)") (class "Default")
      (node (ref "U1") (pin "13") (pinfunction "PF3/FSMC_A3/ADC3_IN9_13") (pintype "passive"))
    )
    (net (code "110") (name "unconnected-(U1-PF4{slash}FSMC_A4{slash}ADC3_IN14-Pad14)") (class "Default")
      (node (ref "U1") (pin "14") (pinfunction "PF4/FSMC_A4/ADC3_IN14_14") (pintype "passive"))
    )
    (net (code "111") (name "unconnected-(U1-PF5{slash}FSMC_A5{slash}ADC3_IN15-Pad15)") (class "Default")
      (node (ref "U1") (pin "15") (pinfunction "PF5/FSMC_A5/ADC3_IN15_15") (pintype "passive"))
    )
    (net (code "112") (name "unconnected-(U1-PF6{slash}TIM10_CH1{slash}FSMC_NIORD{slash}ADC3_IN4-Pad18)") (class "Default")
      (node (ref "U1") (pin "18") (pinfunction "PF6/TIM10_CH1/FSMC_NIORD/ADC3_IN4_18") (pintype "passive"))
    )
    (net (code "113") (name "unconnected-(U1-PF7{slash}TIM11_CH1{slash}FSMC_NREG{slash}ADC3_IN5-Pad19)") (class "Default")
      (node (ref "U1") (pin "19") (pinfunction "PF7/TIM11_CH1/FSMC_NREG/ADC3_IN5_19") (pintype "passive"))
    )
    (net (code "114") (name "unconnected-(U1-PF8{slash}TIM13_CH1{slash}FSMC_NIOWR{slash}ADC3_IN6-Pad20)") (class "Default")
      (node (ref "U1") (pin "20") (pinfunction "PF8/TIM13_CH1/FSMC_NIOWR/ADC3_IN6_20") (pintype "passive"))
    )
    (net (code "115") (name "unconnected-(U1-PF9{slash}TIM14_CH1{slash}FSMC_CD{slash}ADC3_IN7-Pad21)") (class "Default")
      (node (ref "U1") (pin "21") (pinfunction "PF9/TIM14_CH1/FSMC_CD/ADC3_IN7_21") (pintype "passive"))
    )
    (net (code "116") (name "unconnected-(U1-PF10{slash}FSMC_INTR{slash}ADC3_IN8-Pad22)") (class "Default")
      (node (ref "U1") (pin "22") (pinfunction "PF10/FSMC_INTR/ADC3_IN8_22") (pintype "passive"))
    )
    (net (code "117") (name "unconnected-(U1-PF11{slash}DCMI_D12-Pad49)") (class "Default")
      (node (ref "U1") (pin "49") (pinfunction "PF11/DCMI_D12_49") (pintype "passive"))
    )
    (net (code "118") (name "unconnected-(U1-PF12{slash}FSMC_A6-Pad50)") (class "Default")
      (node (ref "U1") (pin "50") (pinfunction "PF12/FSMC_A6_50") (pintype "passive"))
    )
    (net (code "119") (name "unconnected-(U1-PF13{slash}FSMC_A7-Pad53)") (class "Default")
      (node (ref "U1") (pin "53") (pinfunction "PF13/FSMC_A7_53") (pintype "passive"))
    )
    (net (code "120") (name "unconnected-(U1-PF14{slash}FSMC_A8-Pad54)") (class "Default")
      (node (ref "U1") (pin "54") (pinfunction "PF14/FSMC_A8_54") (pintype "passive"))
    )
    (net (code "121") (name "unconnected-(U1-PF15{slash}FSMC_A9-Pad55)") (class "Default")
      (node (ref "U1") (pin "55") (pinfunction "PF15/FSMC_A9_55") (pintype "passive"))
    )
    (net (code "122") (name "unconnected-(U1-PG2{slash}FSMC_A12-Pad87)") (class "Default")
      (node (ref "U1") (pin "87") (pinfunction "PG2/FSMC_A12_87") (pintype "passive"))
    )
    (net (code "123") (name "unconnected-(U1-PG3{slash}FSMC_A13-Pad88)") (class "Default")
      (node (ref "U1") (pin "88") (pinfunction "PG3/FSMC_A13_88") (pintype "passive"))
    )
    (net (code "124") (name "unconnected-(U1-PG4{slash}FSMC_A14-Pad89)") (class "Default")
      (node (ref "U1") (pin "89") (pinfunction "PG4/FSMC_A14_89") (pintype "passive"))
    )
    (net (code "125") (name "unconnected-(U1-PG5{slash}FSMC_A15-Pad90)") (class "Default")
      (node (ref "U1") (pin "90") (pinfunction "PG5/FSMC_A15_90") (pintype "passive"))
    )
    (net (code "126") (name "unconnected-(U1-PG6{slash}FSMC_INT2-Pad91)") (class "Default")
      (node (ref "U1") (pin "91") (pinfunction "PG6/FSMC_INT2_91") (pintype "passive"))
    )
    (net (code "127") (name "unconnected-(U1-PG7{slash}FSMC_INT3{slash}U6_CK-Pad92)") (class "Default")
      (node (ref "U1") (pin "92") (pinfunction "PG7/FSMC_INT3/U6_CK_92") (pintype "passive"))
    )
    (net (code "128") (name "unconnected-(U1-PG8{slash}U6_RTS{slash}ETH_PPS_OUT-Pad93)") (class "Default")
      (node (ref "U1") (pin "93") (pinfunction "PG8/U6_RTS/ETH_PPS_OUT_93") (pintype "passive"))
    )
  )
)
